# MAX31850K_breakout.net
KiCad netlist of a schematic drawn in EAGLE
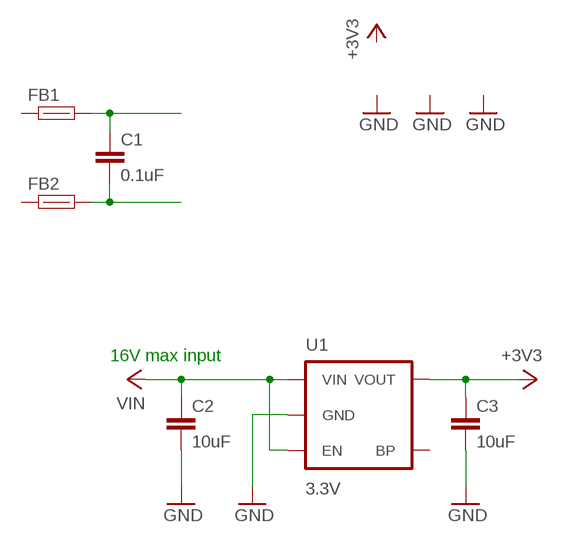
[diagram p0: schematic, sheet 1]

(export (version "E")
  (design (tool "Eeschema 10.0.6"))
  (components
    (comp (ref "C1")
      (value "0.1uF")
      (footprint "eagle-import:0603-CAP")
      (fields
        (field (name "MFR") "Samsung Electro-Mechanics America, Inc")
        (field (name "MPN") "CL10B104KO8NNNC")
      )
      (libsource (lib "eagle-import") (part "0.1UF--?060316V"))
    )
    (comp (ref "C2")
      (value "10uF")
      (footprint "eagle-import:1206-CAP")
      (fields
        (field (name "MFR") "Samsung Electro-Mechanics America, Inc")
        (field (name "MPN") "CL31B106KLHNNNE")
      )
      (libsource (lib "eagle-import") (part "10UF--?120635V"))
    )
    (comp (ref "C3")
      (value "10uF")
      (footprint "eagle-import:0805-CAP")
      (fields
        (field (name "MFR") "Samsung Electro-Mechanics America, Inc")
        (field (name "MPN") "CL21B106KQQNNNE")
      )
      (libsource (lib "eagle-import") (part "10UF--?08056.3V"))
    )
    (comp (ref "FB1")
      (value "FB-1K-100MHZ-0603")
      (footprint "eagle-import:0603-RES")
      (fields
        (field (name "MFR") "Samsung Electro-Mechanics America, Inc.")
        (field (name "MPN") "CIM10J102NC")
      )
      (libsource (lib "eagle-import") (part "FB-1K-100MHZ-?0603"))
    )
    (comp (ref "FB2")
      (value "FB-1K-100MHZ-0603")
      (footprint "eagle-import:0603-RES")
      (fields
        (field (name "MFR") "Samsung Electro-Mechanics America, Inc.")
        (field (name "MPN") "CIM10J102NC")
      )
      (libsource (lib "eagle-import") (part "FB-1K-100MHZ-?0603"))
    )
    (comp (ref "U1")
      (value "3.3V")
      (footprint "eagle-import:SOT23-5")
      (fields (field (name "MFR") "Texas Instruments") (field (name "MPN") "LP2985-33DBVR"))
      (libsource (lib "eagle-import") (part "LP2985-?33DBVR"))
    )
  )
  (nets
    (net (code "1") (name "+3V3") (class "Default")
      (node (ref "C2") (pin "P$3") (pinfunction "1_P$3") (pintype "passive"))
      (node (ref "C3") (pin "P$1") (pinfunction "1_P$1") (pintype "passive"))
      (node (ref "U1") (pin "1") (pinfunction "VIN_1") (pintype "input"))
      (node (ref "U1") (pin "3") (pinfunction "EN_3") (pintype "input"))
      (node (ref "U1") (pin "5") (pinfunction "VOUT_5") (pintype "passive"))
    )
    (net (code "2") (name "GND") (class "Default")
      (node (ref "C2") (pin "P$4") (pinfunction "2_P$4") (pintype "passive"))
      (node (ref "C3") (pin "P$2") (pinfunction "2_P$2") (pintype "passive"))
      (node (ref "U1") (pin "2") (pinfunction "GND_2") (pintype "input"))
    )
    (net (code "3") (name "unconnected-(C1-1-PadP$1)") (class "Default")
      (node (ref "C1") (pin "P$1") (pinfunction "1_P$1") (pintype "passive"))
    )
    (net (code "4") (name "unconnected-(C1-2-PadP$2)") (class "Default")
      (node (ref "C1") (pin "P$2") (pinfunction "2_P$2") (pintype "passive"))
    )
    (net (code "5") (name "unconnected-(FB1-1-PadP$1)") (class "Default")
      (node (ref "FB1") (pin "P$1") (pinfunction "1_P$1") (pintype "passive"))
    )
    (net (code "6") (name "unconnected-(FB1-2-PadP$2)") (class "Default")
      (node (ref "FB1") (pin "P$2") (pinfunction "2_P$2") (pintype "passive"))
    )
    (net (code "7") (name "unconnected-(FB2-1-PadP$1)") (class "Default")
      (node (ref "FB2") (pin "P$1") (pinfunction "1_P$1") (pintype "passive"))
    )
    (net (code "8") (name "unconnected-(FB2-2-PadP$2)") (class "Default")
      (node (ref "FB2") (pin "P$2") (pinfunction "2_P$2") (pintype "passive"))
    )
    (net (code "9") (name "unconnected-(U1-BP-Pad4)") (class "Default")
      (node (ref "U1") (pin "4") (pinfunction "BP_4") (pintype "input"))
    )
  )
)
